# breakout-enc424j600.net
KiCad netlist of a schematic drawn in EAGLE
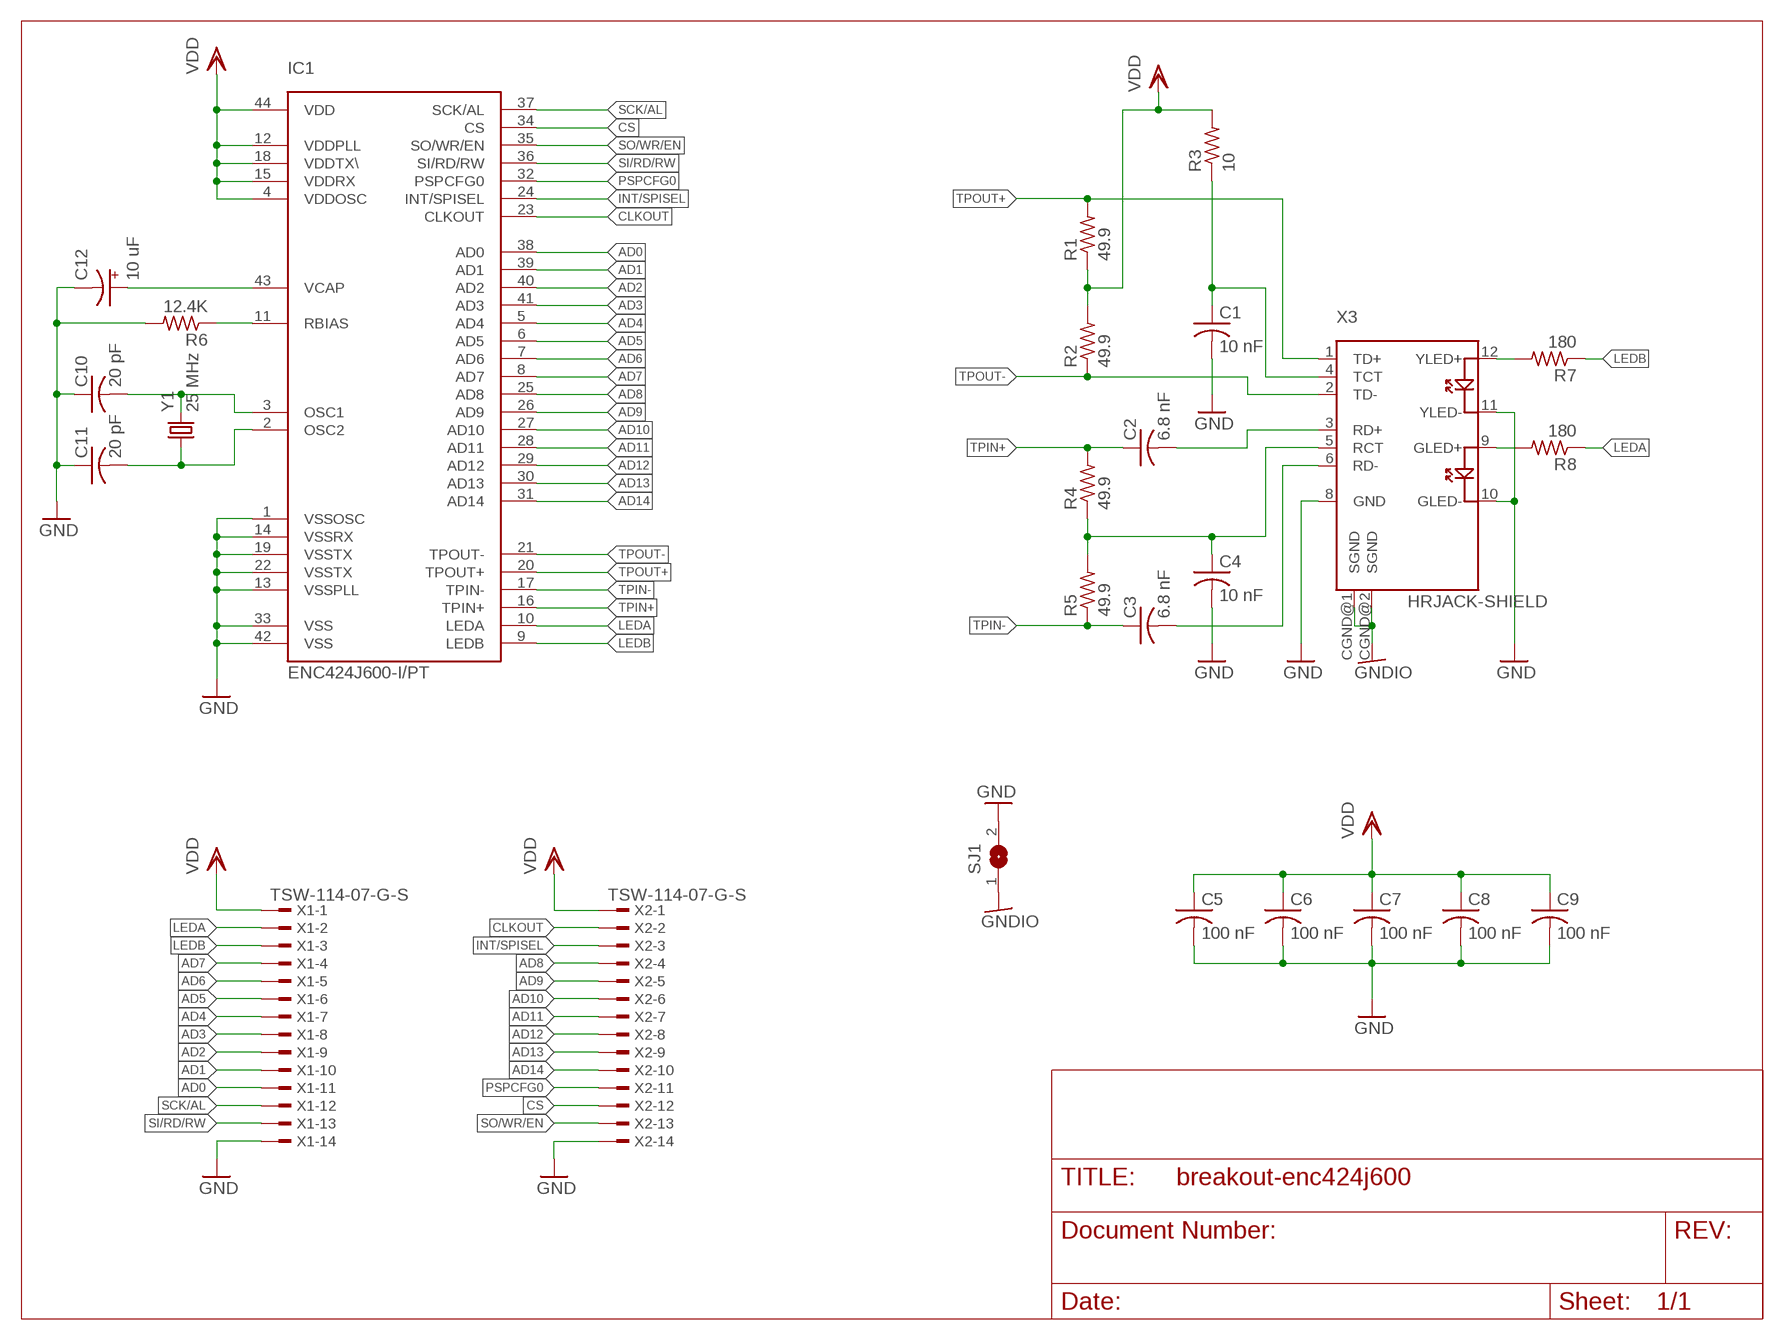
[diagram p0: schematic, sheet 1]

(export (version "E")
  (design (tool "Eeschema 10.0.6"))
  (components
    (comp (ref "C1")
      (value "10 nF")
      (footprint "eagle-import:C0805")
      (libsource (lib "eagle-import") (part "C-USC0805"))
    )
    (comp (ref "C2")
      (value "6.8 nF")
      (footprint "eagle-import:C0805")
      (libsource (lib "eagle-import") (part "C-USC0805"))
    )
    (comp (ref "C3")
      (value "6.8 nF")
      (footprint "eagle-import:C0805")
      (libsource (lib "eagle-import") (part "C-USC0805"))
    )
    (comp (ref "C4")
      (value "10 nF")
      (footprint "eagle-import:C0805")
      (libsource (lib "eagle-import") (part "C-USC0805"))
    )
    (comp (ref "C5")
      (value "100 nF")
      (footprint "eagle-import:C0805")
      (libsource (lib "eagle-import") (part "C-USC0805"))
    )
    (comp (ref "C6")
      (value "100 nF")
      (footprint "eagle-import:C0805")
      (libsource (lib "eagle-import") (part "C-USC0805"))
    )
    (comp (ref "C7")
      (value "100 nF")
      (footprint "eagle-import:C0805")
      (libsource (lib "eagle-import") (part "C-USC0805"))
    )
    (comp (ref "C8")
      (value "100 nF")
      (footprint "eagle-import:C0805")
      (libsource (lib "eagle-import") (part "C-USC0805"))
    )
    (comp (ref "C9")
      (value "100 nF")
      (footprint "eagle-import:C0805")
      (libsource (lib "eagle-import") (part "C-USC0805"))
    )
    (comp (ref "C10")
      (value "20 pF")
      (footprint "eagle-import:C0805")
      (libsource (lib "eagle-import") (part "C-USC0805"))
    )
    (comp (ref "C11")
      (value "20 pF")
      (footprint "eagle-import:C0805")
      (libsource (lib "eagle-import") (part "C-USC0805"))
    )
    (comp (ref "C12")
      (value "10 uF")
      (footprint "eagle-import:SMC_A")
      (libsource (lib "eagle-import") (part "CPOL-USSMCA"))
    )
    (comp (ref "IC1")
      (value "ENC424J600-I/PT")
      (footprint "eagle-import:TQFP44")
      (libsource (lib "eagle-import") (part "ENC424J600-I/PT"))
    )
    (comp (ref "R1")
      (value "49.9")
      (footprint "eagle-import:R0805")
      (libsource (lib "eagle-import") (part "R-US_R0805"))
    )
    (comp (ref "R2")
      (value "49.9")
      (footprint "eagle-import:R0805")
      (libsource (lib "eagle-import") (part "R-US_R0805"))
    )
    (comp (ref "R3")
      (value "10")
      (footprint "eagle-import:R0805")
      (libsource (lib "eagle-import") (part "R-US_R0805"))
    )
    (comp (ref "R4")
      (value "49.9")
      (footprint "eagle-import:R0805")
      (libsource (lib "eagle-import") (part "R-US_R0805"))
    )
    (comp (ref "R5")
      (value "49.9")
      (footprint "eagle-import:R0805")
      (libsource (lib "eagle-import") (part "R-US_R0805"))
    )
    (comp (ref "R6")
      (value "12.4K")
      (footprint "eagle-import:R0805")
      (libsource (lib "eagle-import") (part "R-US_R0805"))
    )
    (comp (ref "R7")
      (value "180")
      (footprint "eagle-import:R0805")
      (libsource (lib "eagle-import") (part "R-US_R0805"))
    )
    (comp (ref "R8")
      (value "180")
      (footprint "eagle-import:R0805")
      (libsource (lib "eagle-import") (part "R-US_R0805"))
    )
    (comp (ref "SJ1")
      (value "SJW")
      (footprint "eagle-import:SJW")
      (libsource (lib "eagle-import") (part "SJW"))
    )
    (comp (ref "X1")
      (value "TSW-114-07-G-S")
      (footprint "eagle-import:TSW-114-XX-G-S")
      (fields (field (name "MF") "Samtec Inc."))
      (libsource (lib "eagle-import") (part "TSW-114--G-S07"))
    )
    (comp (ref "X2")
      (value "TSW-114-07-G-S")
      (footprint "eagle-import:TSW-114-XX-G-S")
      (fields (field (name "MF") "Samtec Inc."))
      (libsource (lib "eagle-import") (part "TSW-114--G-S07"))
    )
    (comp (ref "X3")
      (value "HRJACK-SHIELD")
      (footprint "eagle-import:HR911105A")
      (libsource (lib "eagle-import") (part "HRJACK-SHIELD"))
    )
    (comp (ref "Y1")
      (value "25 MHz")
      (footprint "eagle-import:HC49UP")
      (libsource (lib "eagle-import") (part "CRYSTALHC49UP"))
    )
  )
  (nets
    (net (code "1") (name "AD0") (class "Default")
      (node (ref "IC1") (pin "38") (pinfunction "AD0_38") (pintype "bidirectional"))
      (node (ref "X1") (pin "11") (pinfunction "1_11") (pintype "passive"))
    )
    (net (code "2") (name "AD1") (class "Default")
      (node (ref "IC1") (pin "39") (pinfunction "AD1_39") (pintype "bidirectional"))
      (node (ref "X1") (pin "10") (pinfunction "1_10") (pintype "passive"))
    )
    (net (code "3") (name "AD2") (class "Default")
      (node (ref "IC1") (pin "40") (pinfunction "AD2_40") (pintype "bidirectional"))
      (node (ref "X1") (pin "9") (pinfunction "1_9") (pintype "passive"))
    )
    (net (code "4") (name "AD3") (class "Default")
      (node (ref "IC1") (pin "41") (pinfunction "AD3_41") (pintype "bidirectional"))
      (node (ref "X1") (pin "8") (pinfunction "1_8") (pintype "passive"))
    )
    (net (code "5") (name "AD4") (class "Default")
      (node (ref "IC1") (pin "5") (pinfunction "AD4_5") (pintype "bidirectional"))
      (node (ref "X1") (pin "7") (pinfunction "1_7") (pintype "passive"))
    )
    (net (code "6") (name "AD5") (class "Default")
      (node (ref "IC1") (pin "6") (pinfunction "AD5_6") (pintype "bidirectional"))
      (node (ref "X1") (pin "6") (pinfunction "1_6") (pintype "passive"))
    )
    (net (code "7") (name "AD6") (class "Default")
      (node (ref "IC1") (pin "7") (pinfunction "AD6_7") (pintype "bidirectional"))
      (node (ref "X1") (pin "5") (pinfunction "1_5") (pintype "passive"))
    )
    (net (code "8") (name "AD7") (class "Default")
      (node (ref "IC1") (pin "8") (pinfunction "AD7_8") (pintype "bidirectional"))
      (node (ref "X1") (pin "4") (pinfunction "1_4") (pintype "passive"))
    )
    (net (code "9") (name "AD8") (class "Default")
      (node (ref "IC1") (pin "25") (pinfunction "AD8_25") (pintype "bidirectional"))
      (node (ref "X2") (pin "4") (pinfunction "1_4") (pintype "passive"))
    )
    (net (code "10") (name "AD9") (class "Default")
      (node (ref "IC1") (pin "26") (pinfunction "AD9_26") (pintype "bidirectional"))
      (node (ref "X2") (pin "5") (pinfunction "1_5") (pintype "passive"))
    )
    (net (code "11") (name "AD10") (class "Default")
      (node (ref "IC1") (pin "27") (pinfunction "AD10_27") (pintype "bidirectional"))
      (node (ref "X2") (pin "6") (pinfunction "1_6") (pintype "passive"))
    )
    (net (code "12") (name "AD11") (class "Default")
      (node (ref "IC1") (pin "28") (pinfunction "AD11_28") (pintype "bidirectional"))
      (node (ref "X2") (pin "7") (pinfunction "1_7") (pintype "passive"))
    )
    (net (code "13") (name "AD12") (class "Default")
      (node (ref "IC1") (pin "29") (pinfunction "AD12_29") (pintype "bidirectional"))
      (node (ref "X2") (pin "8") (pinfunction "1_8") (pintype "passive"))
    )
    (net (code "14") (name "AD13") (class "Default")
      (node (ref "IC1") (pin "30") (pinfunction "AD13_30") (pintype "bidirectional"))
      (node (ref "X2") (pin "9") (pinfunction "1_9") (pintype "passive"))
    )
    (net (code "15") (name "AD14") (class "Default")
      (node (ref "IC1") (pin "31") (pinfunction "AD14_31") (pintype "bidirectional"))
      (node (ref "X2") (pin "10") (pinfunction "1_10") (pintype "passive"))
    )
    (net (code "16") (name "CLKOUT") (class "Default")
      (node (ref "IC1") (pin "23") (pinfunction "CLKOUT_23") (pintype "output"))
      (node (ref "X2") (pin "2") (pinfunction "1_2") (pintype "passive"))
    )
    (net (code "17") (name "CS") (class "Default")
      (node (ref "IC1") (pin "34") (pinfunction "CS_34") (pintype "input"))
      (node (ref "X2") (pin "12") (pinfunction "1_12") (pintype "passive"))
    )
    (net (code "18") (name "GND") (class "Default")
      (node (ref "C1") (pin "2") (pinfunction "2_2") (pintype "passive"))
      (node (ref "C10") (pin "1") (pinfunction "1_1") (pintype "passive"))
      (node (ref "C11") (pin "1") (pinfunction "1_1") (pintype "passive"))
      (node (ref "C12") (pin "-") (pinfunction "-_-") (pintype "passive"))
      (node (ref "C4") (pin "2") (pinfunction "2_2") (pintype "passive"))
      (node (ref "C5") (pin "2") (pinfunction "2_2") (pintype "passive"))
      (node (ref "C6") (pin "2") (pinfunction "2_2") (pintype "passive"))
      (node (ref "C7") (pin "2") (pinfunction "2_2") (pintype "passive"))
      (node (ref "C8") (pin "2") (pinfunction "2_2") (pintype "passive"))
      (node (ref "C9") (pin "2") (pinfunction "2_2") (pintype "passive"))
      (node (ref "IC1") (pin "1") (pinfunction "VSSOSC_1") (pintype "power_in"))
      (node (ref "IC1") (pin "13") (pinfunction "VSSPLL_13") (pintype "power_in"))
      (node (ref "IC1") (pin "14") (pinfunction "VSSRX_14") (pintype "power_in"))
      (node (ref "IC1") (pin "19") (pinfunction "VSSTX_19") (pintype "power_in"))
      (node (ref "IC1") (pin "22") (pinfunction "VSSTX_22") (pintype "power_in"))
      (node (ref "IC1") (pin "33") (pinfunction "VSS_33") (pintype "power_in"))
      (node (ref "IC1") (pin "42") (pinfunction "VSS_42") (pintype "power_in"))
      (node (ref "R6") (pin "2") (pinfunction "2_2") (pintype "passive"))
      (node (ref "SJ1") (pin "2") (pinfunction "2_2") (pintype "passive"))
      (node (ref "X1") (pin "14") (pinfunction "1_14") (pintype "passive"))
      (node (ref "X2") (pin "14") (pinfunction "1_14") (pintype "passive"))
      (node (ref "X3") (pin "10") (pinfunction "GLED-_10") (pintype "passive"))
      (node (ref "X3") (pin "11") (pinfunction "YLED-_11") (pintype "passive"))
      (node (ref "X3") (pin "8") (pinfunction "GND_8") (pintype "bidirectional"))
    )
    (net (code "19") (name "GNDIO") (class "Default")
      (node (ref "SJ1") (pin "1") (pinfunction "1_1") (pintype "passive"))
      (node (ref "X3") (pin "CGND@1") (pinfunction "SGND_CGND@1") (pintype "bidirectional"))
      (node (ref "X3") (pin "CGND@2") (pinfunction "SGND_CGND@2") (pintype "bidirectional"))
    )
    (net (code "20") (name "INT{slash}SPISEL") (class "Default")
      (node (ref "IC1") (pin "24") (pinfunction "INT/SPISEL_24") (pintype "bidirectional"))
      (node (ref "X2") (pin "3") (pinfunction "1_3") (pintype "passive"))
    )
    (net (code "21") (name "LEDA") (class "Default")
      (node (ref "IC1") (pin "10") (pinfunction "LEDA_10") (pintype "output"))
      (node (ref "R8") (pin "1") (pinfunction "1_1") (pintype "passive"))
      (node (ref "X1") (pin "2") (pinfunction "1_2") (pintype "passive"))
    )
    (net (code "22") (name "LEDB") (class "Default")
      (node (ref "IC1") (pin "9") (pinfunction "LEDB_9") (pintype "output"))
      (node (ref "R7") (pin "1") (pinfunction "1_1") (pintype "passive"))
      (node (ref "X1") (pin "3") (pinfunction "1_3") (pintype "passive"))
    )
    (net (code "23") (name "Net-(IC1-OSC1)") (class "Default")
      (node (ref "C10") (pin "2") (pinfunction "2_2") (pintype "passive"))
      (node (ref "IC1") (pin "3") (pinfunction "OSC1_3") (pintype "bidirectional"))
      (node (ref "Y1") (pin "2") (pinfunction "2_2") (pintype "passive"))
    )
    (net (code "24") (name "Net-(IC1-OSC2)") (class "Default")
      (node (ref "C11") (pin "2") (pinfunction "2_2") (pintype "passive"))
      (node (ref "IC1") (pin "2") (pinfunction "OSC2_2") (pintype "bidirectional"))
      (node (ref "Y1") (pin "1") (pinfunction "1_1") (pintype "passive"))
    )
    (net (code "25") (name "Net-(IC1-RBIAS)") (class "Default")
      (node (ref "IC1") (pin "11") (pinfunction "RBIAS_11") (pintype "bidirectional"))
      (node (ref "R6") (pin "1") (pinfunction "1_1") (pintype "passive"))
    )
    (net (code "26") (name "Net-(IC1-VCAP)") (class "Default")
      (node (ref "C12") (pin "+") (pinfunction "+_+") (pintype "passive"))
      (node (ref "IC1") (pin "43") (pinfunction "VCAP_43") (pintype "bidirectional"))
    )
    (net (code "27") (name "Net-(X3-GLED+)") (class "Default")
      (node (ref "R8") (pin "2") (pinfunction "2_2") (pintype "passive"))
      (node (ref "X3") (pin "9") (pinfunction "GLED+_9") (pintype "passive"))
    )
    (net (code "28") (name "Net-(X3-RCT)") (class "Default")
      (node (ref "C4") (pin "1") (pinfunction "1_1") (pintype "passive"))
      (node (ref "R4") (pin "1") (pinfunction "1_1") (pintype "passive"))
      (node (ref "R5") (pin "2") (pinfunction "2_2") (pintype "passive"))
      (node (ref "X3") (pin "5") (pinfunction "RCT_5") (pintype "passive"))
    )
    (net (code "29") (name "Net-(X3-RD+)") (class "Default")
      (node (ref "C2") (pin "2") (pinfunction "2_2") (pintype "passive"))
      (node (ref "X3") (pin "3") (pinfunction "RD+_3") (pintype "passive"))
    )
    (net (code "30") (name "Net-(X3-RD-)") (class "Default")
      (node (ref "C3") (pin "2") (pinfunction "2_2") (pintype "passive"))
      (node (ref "X3") (pin "6") (pinfunction "RD-_6") (pintype "passive"))
    )
    (net (code "31") (name "Net-(X3-TCT)") (class "Default")
      (node (ref "C1") (pin "1") (pinfunction "1_1") (pintype "passive"))
      (node (ref "R3") (pin "1") (pinfunction "1_1") (pintype "passive"))
      (node (ref "X3") (pin "4") (pinfunction "TCT_4") (pintype "passive"))
    )
    (net (code "32") (name "Net-(X3-YLED+)") (class "Default")
      (node (ref "R7") (pin "2") (pinfunction "2_2") (pintype "passive"))
      (node (ref "X3") (pin "12") (pinfunction "YLED+_12") (pintype "passive"))
    )
    (net (code "33") (name "PSPCFG0") (class "Default")
      (node (ref "IC1") (pin "32") (pinfunction "PSPCFG0_32") (pintype "input"))
      (node (ref "X2") (pin "11") (pinfunction "1_11") (pintype "passive"))
    )
    (net (code "34") (name "SCK{slash}AL") (class "Default")
      (node (ref "IC1") (pin "37") (pinfunction "SCK/AL_37") (pintype "input"))
      (node (ref "X1") (pin "12") (pinfunction "1_12") (pintype "passive"))
    )
    (net (code "35") (name "SI{slash}RD{slash}RW") (class "Default")
      (node (ref "IC1") (pin "36") (pinfunction "SI/RD/RW_36") (pintype "bidirectional"))
      (node (ref "X1") (pin "13") (pinfunction "1_13") (pintype "passive"))
    )
    (net (code "36") (name "SO{slash}WR{slash}EN") (class "Default")
      (node (ref "IC1") (pin "35") (pinfunction "SO/WR/EN_35") (pintype "bidirectional"))
      (node (ref "X2") (pin "13") (pinfunction "1_13") (pintype "passive"))
    )
    (net (code "37") (name "TPIN+") (class "Default")
      (node (ref "C2") (pin "1") (pinfunction "1_1") (pintype "passive"))
      (node (ref "IC1") (pin "16") (pinfunction "TPIN+_16") (pintype "input"))
      (node (ref "R4") (pin "2") (pinfunction "2_2") (pintype "passive"))
    )
    (net (code "38") (name "TPIN-") (class "Default")
      (node (ref "C3") (pin "1") (pinfunction "1_1") (pintype "passive"))
      (node (ref "IC1") (pin "17") (pinfunction "TPIN-_17") (pintype "input"))
      (node (ref "R5") (pin "1") (pinfunction "1_1") (pintype "passive"))
    )
    (net (code "39") (name "TPOUT+") (class "Default")
      (node (ref "IC1") (pin "20") (pinfunction "TPOUT+_20") (pintype "output"))
      (node (ref "R1") (pin "2") (pinfunction "2_2") (pintype "passive"))
      (node (ref "X3") (pin "1") (pinfunction "TD+_1") (pintype "passive"))
    )
    (net (code "40") (name "TPOUT-") (class "Default")
      (node (ref "IC1") (pin "21") (pinfunction "TPOUT-_21") (pintype "output"))
      (node (ref "R2") (pin "1") (pinfunction "1_1") (pintype "passive"))
      (node (ref "X3") (pin "2") (pinfunction "TD-_2") (pintype "passive"))
    )
    (net (code "41") (name "VDD") (class "Default")
      (node (ref "C5") (pin "1") (pinfunction "1_1") (pintype "passive"))
      (node (ref "C6") (pin "1") (pinfunction "1_1") (pintype "passive"))
      (node (ref "C7") (pin "1") (pinfunction "1_1") (pintype "passive"))
      (node (ref "C8") (pin "1") (pinfunction "1_1") (pintype "passive"))
      (node (ref "C9") (pin "1") (pinfunction "1_1") (pintype "passive"))
      (node (ref "IC1") (pin "12") (pinfunction "VDDPLL_12") (pintype "power_in"))
      (node (ref "IC1") (pin "15") (pinfunction "VDDRX_15") (pintype "power_in"))
      (node (ref "IC1") (pin "18") (pinfunction "VDDTX\\_18") (pintype "power_in"))
      (node (ref "IC1") (pin "4") (pinfunction "VDDOSC_4") (pintype "power_in"))
      (node (ref "IC1") (pin "44") (pinfunction "VDD_44") (pintype "power_in"))
      (node (ref "R1") (pin "1") (pinfunction "1_1") (pintype "passive"))
      (node (ref "R2") (pin "2") (pinfunction "2_2") (pintype "passive"))
      (node (ref "R3") (pin "2") (pinfunction "2_2") (pintype "passive"))
      (node (ref "X1") (pin "1") (pinfunction "1_1") (pintype "passive"))
      (node (ref "X2") (pin "1") (pinfunction "1_1") (pintype "passive"))
    )
  )
)
